# POWER.net
KiCad netlist of a schematic drawn in Altium Designer
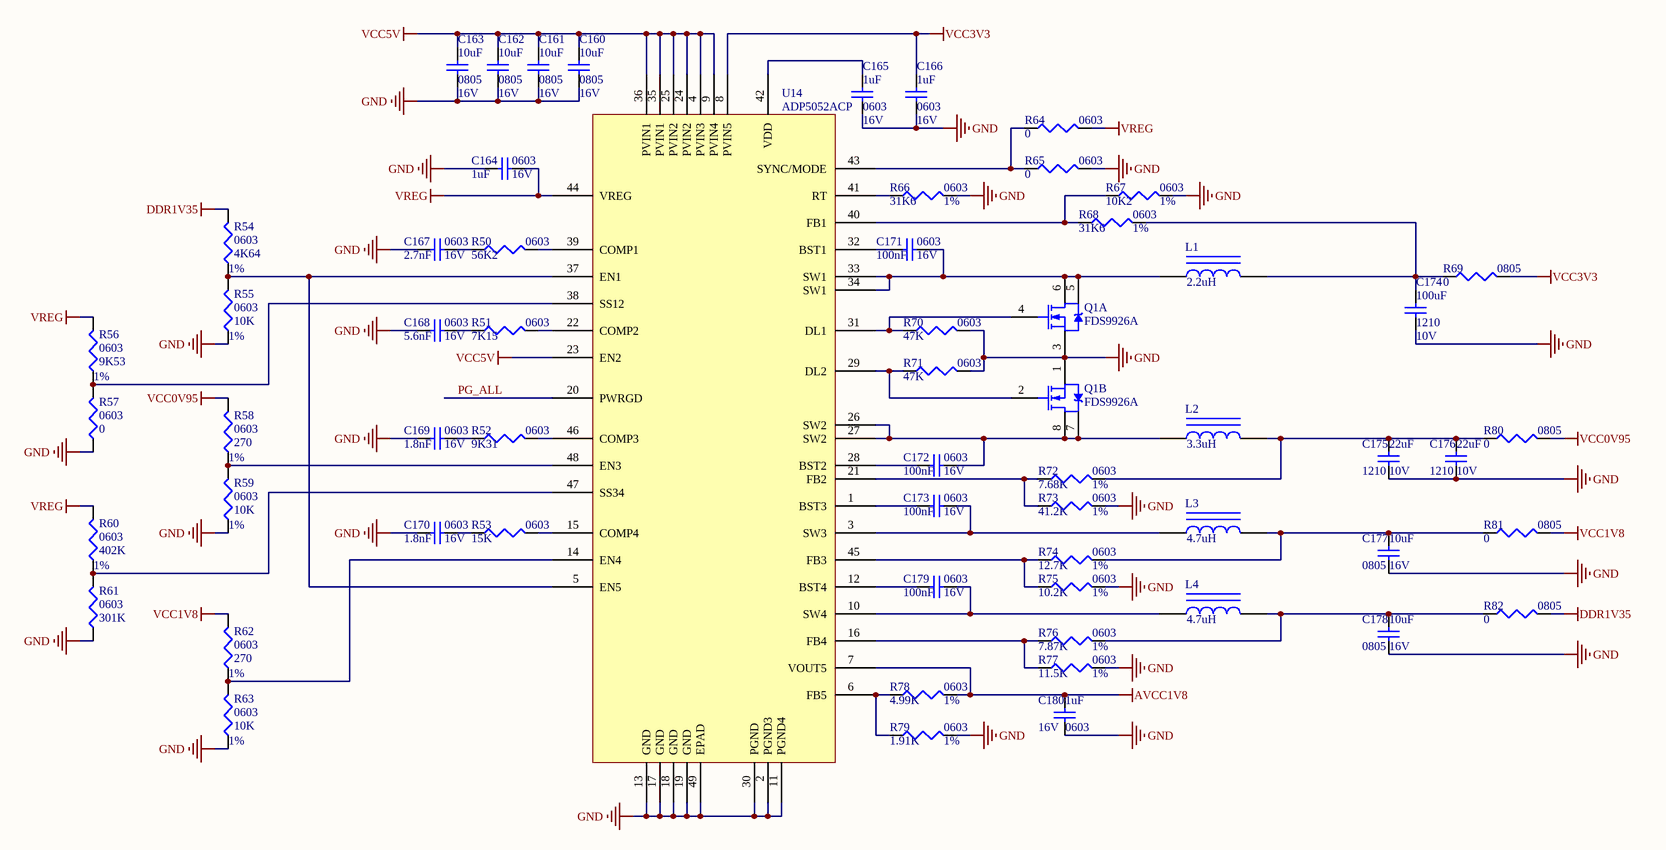
[diagram p0: POWER.SchDoc]

(export (version "E")
  (design (tool "Eeschema 10.0.6"))
  (components
    (comp (ref "C160")
      (value "10uF")
      (footprint "2012[0805]")
      (description "Capacitor (Semiconductor SIM Model)")
      (fields
        (field (name "PACKAGEREFERENCE") "0805")
        (field (name "V") "16V")
        (field (name "PUBLISHER") "Altium Limited")
      )
      (libsource (lib "Devices") (part "Cap Semi"))
    )
    (comp (ref "C161")
      (value "10uF")
      (footprint "2012[0805]")
      (description "Capacitor (Semiconductor SIM Model)")
      (fields
        (field (name "PACKAGEREFERENCE") "0805")
        (field (name "V") "16V")
        (field (name "PUBLISHER") "Altium Limited")
      )
      (libsource (lib "Devices") (part "Cap Semi"))
    )
    (comp (ref "C162")
      (value "10uF")
      (footprint "2012[0805]")
      (description "Capacitor (Semiconductor SIM Model)")
      (fields
        (field (name "PACKAGEREFERENCE") "0805")
        (field (name "V") "16V")
        (field (name "PUBLISHER") "Altium Limited")
      )
      (libsource (lib "Devices") (part "Cap Semi"))
    )
    (comp (ref "C163")
      (value "10uF")
      (footprint "2012[0805]")
      (description "Capacitor (Semiconductor SIM Model)")
      (fields
        (field (name "PACKAGEREFERENCE") "0805")
        (field (name "V") "16V")
        (field (name "PUBLISHER") "Altium Limited")
      )
      (libsource (lib "Devices") (part "Cap Semi"))
    )
    (comp (ref "C164")
      (value "1uF")
      (footprint "1608[0603]")
      (description "Capacitor (Semiconductor SIM Model)")
      (fields
        (field (name "PACKAGEREFERENCE") "0603")
        (field (name "V") "16V")
        (field (name "PUBLISHER") "Altium Limited")
      )
      (libsource (lib "Devices") (part "Cap Semi"))
    )
    (comp (ref "C165")
      (value "1uF")
      (footprint "1608[0603]")
      (description "Capacitor (Semiconductor SIM Model)")
      (fields
        (field (name "PACKAGEREFERENCE") "0603")
        (field (name "V") "16V")
        (field (name "PUBLISHER") "Altium Limited")
      )
      (libsource (lib "Devices") (part "Cap Semi"))
    )
    (comp (ref "C166")
      (value "1uF")
      (footprint "1608[0603]")
      (description "Capacitor (Semiconductor SIM Model)")
      (fields
        (field (name "PACKAGEREFERENCE") "0603")
        (field (name "V") "16V")
        (field (name "PUBLISHER") "Altium Limited")
      )
      (libsource (lib "Devices") (part "Cap Semi"))
    )
    (comp (ref "C167")
      (value "2.7nF")
      (footprint "1608[0603]")
      (description "Capacitor (Semiconductor SIM Model)")
      (fields
        (field (name "PACKAGEREFERENCE") "0603")
        (field (name "V") "16V")
        (field (name "PUBLISHER") "Altium Limited")
      )
      (libsource (lib "Devices") (part "Cap Semi"))
    )
    (comp (ref "C168")
      (value "5.6nF")
      (footprint "1608[0603]")
      (description "Capacitor (Semiconductor SIM Model)")
      (fields
        (field (name "PACKAGEREFERENCE") "0603")
        (field (name "V") "16V")
        (field (name "PUBLISHER") "Altium Limited")
      )
      (libsource (lib "Devices") (part "Cap Semi"))
    )
    (comp (ref "C169")
      (value "1.8nF")
      (footprint "1608[0603]")
      (description "Capacitor (Semiconductor SIM Model)")
      (fields
        (field (name "PACKAGEREFERENCE") "0603")
        (field (name "V") "16V")
        (field (name "PUBLISHER") "Altium Limited")
      )
      (libsource (lib "Devices") (part "Cap Semi"))
    )
    (comp (ref "C170")
      (value "1.8nF")
      (footprint "1608[0603]")
      (description "Capacitor (Semiconductor SIM Model)")
      (fields
        (field (name "PACKAGEREFERENCE") "0603")
        (field (name "V") "16V")
        (field (name "PUBLISHER") "Altium Limited")
      )
      (libsource (lib "Devices") (part "Cap Semi"))
    )
    (comp (ref "C171")
      (value "100nF")
      (footprint "1608[0603]")
      (description "Capacitor (Semiconductor SIM Model)")
      (fields
        (field (name "PACKAGEREFERENCE") "0603")
        (field (name "V") "16V")
        (field (name "PUBLISHER") "Altium Limited")
      )
      (libsource (lib "Devices") (part "Cap Semi"))
    )
    (comp (ref "C172")
      (value "100nF")
      (footprint "1608[0603]")
      (description "Capacitor (Semiconductor SIM Model)")
      (fields
        (field (name "PACKAGEREFERENCE") "0603")
        (field (name "V") "16V")
        (field (name "PUBLISHER") "Altium Limited")
      )
      (libsource (lib "Devices") (part "Cap Semi"))
    )
    (comp (ref "C173")
      (value "100nF")
      (footprint "1608[0603]")
      (description "Capacitor (Semiconductor SIM Model)")
      (fields
        (field (name "PACKAGEREFERENCE") "0603")
        (field (name "V") "16V")
        (field (name "PUBLISHER") "Altium Limited")
      )
      (libsource (lib "Devices") (part "Cap Semi"))
    )
    (comp (ref "C174")
      (value "100uF")
      (footprint "2012[0805]")
      (description "Capacitor (Semiconductor SIM Model)")
      (fields
        (field (name "PACKAGEREFERENCE") "1210")
        (field (name "V") "10V")
        (field (name "PUBLISHER") "Altium Limited")
      )
      (libsource (lib "Devices") (part "Cap Semi"))
    )
    (comp (ref "C175")
      (value "22uF")
      (footprint "2012[0805]")
      (description "Capacitor (Semiconductor SIM Model)")
      (fields
        (field (name "PACKAGEREFERENCE") "1210")
        (field (name "V") "10V")
        (field (name "PUBLISHER") "Altium Limited")
      )
      (libsource (lib "Devices") (part "Cap Semi"))
    )
    (comp (ref "C176")
      (value "22uF")
      (footprint "2012[0805]")
      (description "Capacitor (Semiconductor SIM Model)")
      (fields
        (field (name "PACKAGEREFERENCE") "1210")
        (field (name "V") "10V")
        (field (name "PUBLISHER") "Altium Limited")
      )
      (libsource (lib "Devices") (part "Cap Semi"))
    )
    (comp (ref "C177")
      (value "10uF")
      (footprint "2012[0805]")
      (description "Capacitor (Semiconductor SIM Model)")
      (fields
        (field (name "PACKAGEREFERENCE") "0805")
        (field (name "V") "16V")
        (field (name "PUBLISHER") "Altium Limited")
      )
      (libsource (lib "Devices") (part "Cap Semi"))
    )
    (comp (ref "C178")
      (value "10uF")
      (footprint "2012[0805]")
      (description "Capacitor (Semiconductor SIM Model)")
      (fields
        (field (name "PACKAGEREFERENCE") "0805")
        (field (name "V") "16V")
        (field (name "PUBLISHER") "Altium Limited")
      )
      (libsource (lib "Devices") (part "Cap Semi"))
    )
    (comp (ref "C179")
      (value "100nF")
      (footprint "1608[0603]")
      (description "Capacitor (Semiconductor SIM Model)")
      (fields
        (field (name "PACKAGEREFERENCE") "0603")
        (field (name "V") "16V")
        (field (name "PUBLISHER") "Altium Limited")
      )
      (libsource (lib "Devices") (part "Cap Semi"))
    )
    (comp (ref "C180")
      (value "1uF")
      (footprint "1608[0603]")
      (description "Capacitor (Semiconductor SIM Model)")
      (fields
        (field (name "PACKAGEREFERENCE") "0603")
        (field (name "V") "16V")
        (field (name "PUBLISHER") "Altium Limited")
      )
      (libsource (lib "Devices") (part "Cap Semi"))
    )
    (comp (ref "L1")
      (value "2.2uH")
      (footprint "SRN6045")
      (description "Magnetic-Core Inductor")
      (fields (field (name "Comment") "Inductor Iron") (field (name "PUBLISHER") "Altium Limited"))
      (libsource (lib "Miscellaneous Devices") (part "Inductor Iron"))
    )
    (comp (ref "L2")
      (value "3.3uH")
      (footprint "SRN4018")
      (description "Magnetic-Core Inductor")
      (fields (field (name "Comment") "Inductor Iron") (field (name "PUBLISHER") "Altium Limited"))
      (libsource (lib "Miscellaneous Devices") (part "Inductor Iron"))
    )
    (comp (ref "L3")
      (value "4.7uH")
      (footprint "SRN4018")
      (description "Magnetic-Core Inductor")
      (fields (field (name "Comment") "Inductor Iron") (field (name "PUBLISHER") "Altium Limited"))
      (libsource (lib "Miscellaneous Devices") (part "Inductor Iron"))
    )
    (comp (ref "L4")
      (value "4.7uH")
      (footprint "SRN4018")
      (description "Magnetic-Core Inductor")
      (fields (field (name "Comment") "Inductor Iron") (field (name "PUBLISHER") "Altium Limited"))
      (libsource (lib "Miscellaneous Devices") (part "Inductor Iron"))
    )
    (comp (ref "Q1")
      (value "FDS9926A")
      (footprint "FDS9926A")
      (libsource (lib "Spartan6_LX9_A0") (part "FDS9926A"))
    )
    (comp (ref "R50")
      (value "56K2")
      (footprint "1608[0603]")
      (description "Resistor")
      (fields
        (field (name "PACKAGEREFERENCE") "0603")
        (field (name "Comment") "Res3")
        (field (name "PUBLISHER") "Altium Limited")
      )
      (libsource (lib "Miscellaneous Devices") (part "Res3"))
    )
    (comp (ref "R51")
      (value "7K15")
      (footprint "1608[0603]")
      (description "Resistor")
      (fields
        (field (name "PACKAGEREFERENCE") "0603")
        (field (name "Comment") "Res3")
        (field (name "PUBLISHER") "Altium Limited")
      )
      (libsource (lib "Miscellaneous Devices") (part "Res3"))
    )
    (comp (ref "R52")
      (value "9K31")
      (footprint "1608[0603]")
      (description "Resistor")
      (fields
        (field (name "PACKAGEREFERENCE") "0603")
        (field (name "Comment") "Res3")
        (field (name "PUBLISHER") "Altium Limited")
      )
      (libsource (lib "Miscellaneous Devices") (part "Res3"))
    )
    (comp (ref "R53")
      (value "15K")
      (footprint "1608[0603]")
      (description "Resistor")
      (fields
        (field (name "PACKAGEREFERENCE") "0603")
        (field (name "Comment") "Res3")
        (field (name "PUBLISHER") "Altium Limited")
      )
      (libsource (lib "Miscellaneous Devices") (part "Res3"))
    )
    (comp (ref "R54")
      (value "4K64")
      (footprint "1608[0603]")
      (description "Resistor")
      (fields
        (field (name "PACKAGEREFERENCE") "0603")
        (field (name "AC") "1%")
        (field (name "Comment") "Res3")
        (field (name "PUBLISHER") "Altium Limited")
      )
      (libsource (lib "Miscellaneous Devices") (part "Res3"))
    )
    (comp (ref "R55")
      (value "10K")
      (footprint "1608[0603]")
      (description "Resistor")
      (fields
        (field (name "PACKAGEREFERENCE") "0603")
        (field (name "AC") "1%")
        (field (name "Comment") "Res3")
        (field (name "PUBLISHER") "Altium Limited")
      )
      (libsource (lib "Miscellaneous Devices") (part "Res3"))
    )
    (comp (ref "R56")
      (value "9K53")
      (footprint "1608[0603]")
      (description "Resistor")
      (fields
        (field (name "PACKAGEREFERENCE") "0603")
        (field (name "AC") "1%")
        (field (name "Comment") "Res3")
        (field (name "PUBLISHER") "Altium Limited")
      )
      (libsource (lib "Miscellaneous Devices") (part "Res3"))
    )
    (comp (ref "R57")
      (value "0")
      (footprint "1608[0603]")
      (description "Resistor")
      (fields
        (field (name "PACKAGEREFERENCE") "0603")
        (field (name "Comment") "Res3")
        (field (name "PUBLISHER") "Altium Limited")
      )
      (libsource (lib "Miscellaneous Devices") (part "Res3"))
    )
    (comp (ref "R58")
      (value "270")
      (footprint "1608[0603]")
      (description "Resistor")
      (fields
        (field (name "PACKAGEREFERENCE") "0603")
        (field (name "AC") "1%")
        (field (name "Comment") "Res3")
        (field (name "PUBLISHER") "Altium Limited")
      )
      (libsource (lib "Miscellaneous Devices") (part "Res3"))
    )
    (comp (ref "R59")
      (value "10K")
      (footprint "1608[0603]")
      (description "Resistor")
      (fields
        (field (name "PACKAGEREFERENCE") "0603")
        (field (name "AC") "1%")
        (field (name "Comment") "Res3")
        (field (name "PUBLISHER") "Altium Limited")
      )
      (libsource (lib "Miscellaneous Devices") (part "Res3"))
    )
    (comp (ref "R60")
      (value "402K")
      (footprint "1608[0603]")
      (description "Resistor")
      (fields
        (field (name "PACKAGEREFERENCE") "0603")
        (field (name "AC") "1%")
        (field (name "Comment") "Res3")
        (field (name "PUBLISHER") "Altium Limited")
      )
      (libsource (lib "Miscellaneous Devices") (part "Res3"))
    )
    (comp (ref "R61")
      (value "301K")
      (footprint "1608[0603]")
      (description "Resistor")
      (fields
        (field (name "PACKAGEREFERENCE") "0603")
        (field (name "Comment") "Res3")
        (field (name "PUBLISHER") "Altium Limited")
      )
      (libsource (lib "Miscellaneous Devices") (part "Res3"))
    )
    (comp (ref "R62")
      (value "270")
      (footprint "1608[0603]")
      (description "Resistor")
      (fields
        (field (name "PACKAGEREFERENCE") "0603")
        (field (name "AC") "1%")
        (field (name "Comment") "Res3")
        (field (name "PUBLISHER") "Altium Limited")
      )
      (libsource (lib "Miscellaneous Devices") (part "Res3"))
    )
    (comp (ref "R63")
      (value "10K")
      (footprint "1608[0603]")
      (description "Resistor")
      (fields
        (field (name "PACKAGEREFERENCE") "0603")
        (field (name "AC") "1%")
        (field (name "Comment") "Res3")
        (field (name "PUBLISHER") "Altium Limited")
      )
      (libsource (lib "Miscellaneous Devices") (part "Res3"))
    )
    (comp (ref "R64")
      (value "0")
      (footprint "1608[0603]")
      (description "Resistor")
      (fields
        (field (name "PACKAGEREFERENCE") "0603")
        (field (name "Comment") "Res3")
        (field (name "PUBLISHER") "Altium Limited")
      )
      (libsource (lib "Miscellaneous Devices") (part "Res3"))
    )
    (comp (ref "R65")
      (value "0")
      (footprint "1608[0603]")
      (description "Resistor")
      (fields
        (field (name "PACKAGEREFERENCE") "0603")
        (field (name "Comment") "Res3")
        (field (name "PUBLISHER") "Altium Limited")
      )
      (libsource (lib "Miscellaneous Devices") (part "Res3"))
    )
    (comp (ref "R66")
      (value "31K6")
      (footprint "1608[0603]")
      (description "Resistor")
      (fields
        (field (name "PACKAGEREFERENCE") "0603")
        (field (name "AC") "1%")
        (field (name "Comment") "Res3")
        (field (name "PUBLISHER") "Altium Limited")
      )
      (libsource (lib "Miscellaneous Devices") (part "Res3"))
    )
    (comp (ref "R67")
      (value "10K2")
      (footprint "1608[0603]")
      (description "Resistor")
      (fields
        (field (name "PACKAGEREFERENCE") "0603")
        (field (name "AC") "1%")
        (field (name "Comment") "Res3")
        (field (name "PUBLISHER") "Altium Limited")
      )
      (libsource (lib "Miscellaneous Devices") (part "Res3"))
    )
    (comp (ref "R68")
      (value "31K6")
      (footprint "1608[0603]")
      (description "Resistor")
      (fields
        (field (name "PACKAGEREFERENCE") "0603")
        (field (name "AC") "1%")
        (field (name "Comment") "Res3")
        (field (name "PUBLISHER") "Altium Limited")
      )
      (libsource (lib "Miscellaneous Devices") (part "Res3"))
    )
    (comp (ref "R69")
      (value "0")
      (footprint "2012[0805]")
      (description "Resistor")
      (fields
        (field (name "PACKAGEREFERENCE") "0805")
        (field (name "Comment") "Res3")
        (field (name "PUBLISHER") "Altium Limited")
      )
      (libsource (lib "Miscellaneous Devices") (part "Res3"))
    )
    (comp (ref "R70")
      (value "47K")
      (footprint "1608[0603]")
      (description "Resistor")
      (fields
        (field (name "PACKAGEREFERENCE") "0603")
        (field (name "Comment") "Res3")
        (field (name "PUBLISHER") "Altium Limited")
      )
      (libsource (lib "Miscellaneous Devices") (part "Res3"))
    )
    (comp (ref "R71")
      (value "47K")
      (footprint "1608[0603]")
      (description "Resistor")
      (fields
        (field (name "PACKAGEREFERENCE") "0603")
        (field (name "Comment") "Res3")
        (field (name "PUBLISHER") "Altium Limited")
      )
      (libsource (lib "Miscellaneous Devices") (part "Res3"))
    )
    (comp (ref "R72")
      (value "7.68K")
      (footprint "1608[0603]")
      (description "Resistor")
      (fields
        (field (name "PACKAGEREFERENCE") "0603")
        (field (name "AC") "1%")
        (field (name "Comment") "Res3")
        (field (name "PUBLISHER") "Altium Limited")
      )
      (libsource (lib "Miscellaneous Devices") (part "Res3"))
    )
    (comp (ref "R73")
      (value "41.2K")
      (footprint "1608[0603]")
      (description "Resistor")
      (fields
        (field (name "PACKAGEREFERENCE") "0603")
        (field (name "AC") "1%")
        (field (name "Comment") "Res3")
        (field (name "PUBLISHER") "Altium Limited")
      )
      (libsource (lib "Miscellaneous Devices") (part "Res3"))
    )
    (comp (ref "R74")
      (value "12.7K")
      (footprint "1608[0603]")
      (description "Resistor")
      (fields
        (field (name "PACKAGEREFERENCE") "0603")
        (field (name "AC") "1%")
        (field (name "Comment") "Res3")
        (field (name "PUBLISHER") "Altium Limited")
      )
      (libsource (lib "Miscellaneous Devices") (part "Res3"))
    )
    (comp (ref "R75")
      (value "10.2K")
      (footprint "1608[0603]")
      (description "Resistor")
      (fields
        (field (name "PACKAGEREFERENCE") "0603")
        (field (name "AC") "1%")
        (field (name "Comment") "Res3")
        (field (name "PUBLISHER") "Altium Limited")
      )
      (libsource (lib "Miscellaneous Devices") (part "Res3"))
    )
    (comp (ref "R76")
      (value "7.87K")
      (footprint "1608[0603]")
      (description "Resistor")
      (fields
        (field (name "PACKAGEREFERENCE") "0603")
        (field (name "AC") "1%")
        (field (name "Comment") "Res3")
        (field (name "PUBLISHER") "Altium Limited")
      )
      (libsource (lib "Miscellaneous Devices") (part "Res3"))
    )
    (comp (ref "R77")
      (value "11.5K")
      (footprint "1608[0603]")
      (description "Resistor")
      (fields
        (field (name "PACKAGEREFERENCE") "0603")
        (field (name "AC") "1%")
        (field (name "Comment") "Res3")
        (field (name "PUBLISHER") "Altium Limited")
      )
      (libsource (lib "Miscellaneous Devices") (part "Res3"))
    )
    (comp (ref "R78")
      (value "4.99K")
      (footprint "1608[0603]")
      (description "Resistor")
      (fields
        (field (name "PACKAGEREFERENCE") "0603")
        (field (name "AC") "1%")
        (field (name "Comment") "Res3")
        (field (name "PUBLISHER") "Altium Limited")
      )
      (libsource (lib "Miscellaneous Devices") (part "Res3"))
    )
    (comp (ref "R79")
      (value "1.91K")
      (footprint "1608[0603]")
      (description "Resistor")
      (fields
        (field (name "PACKAGEREFERENCE") "0603")
        (field (name "AC") "1%")
        (field (name "Comment") "Res3")
        (field (name "PUBLISHER") "Altium Limited")
      )
      (libsource (lib "Miscellaneous Devices") (part "Res3"))
    )
    (comp (ref "R80")
      (value "0")
      (footprint "2012[0805]")
      (description "Resistor")
      (fields
        (field (name "PACKAGEREFERENCE") "0805")
        (field (name "Comment") "Res3")
        (field (name "PUBLISHER") "Altium Limited")
      )
      (libsource (lib "Miscellaneous Devices") (part "Res3"))
    )
    (comp (ref "R81")
      (value "0")
      (footprint "2012[0805]")
      (description "Resistor")
      (fields
        (field (name "PACKAGEREFERENCE") "0805")
        (field (name "Comment") "Res3")
        (field (name "PUBLISHER") "Altium Limited")
      )
      (libsource (lib "Miscellaneous Devices") (part "Res3"))
    )
    (comp (ref "R82")
      (value "0")
      (footprint "2012[0805]")
      (description "Resistor")
      (fields
        (field (name "PACKAGEREFERENCE") "0805")
        (field (name "Comment") "Res3")
        (field (name "PUBLISHER") "Altium Limited")
      )
      (libsource (lib "Miscellaneous Devices") (part "Res3"))
    )
    (comp (ref "U14")
      (value "ADP5052ACP")
      (footprint "ADP5052")
      (libsource (lib "Spartan6_LX9_A0") (part "ADP5052ACP{backslash}"))
    )
  )
  (nets
    (net (code "1") (name "/PG_ALL") (class "Default")
      (node (ref "U14") (pin "20") (pinfunction "PWRGD_20") (pintype "passive"))
    )
    (net (code "2") (name "AVCC1V8") (class "Default")
      (node (ref "C180") (pin "1") (pinfunction "1_1") (pintype "passive"))
      (node (ref "R78") (pin "2") (pinfunction "2_2") (pintype "passive"))
      (node (ref "U14") (pin "7") (pinfunction "VOUT5_7") (pintype "passive"))
    )
    (net (code "3") (name "DDR1V35") (class "Default")
      (node (ref "R54") (pin "2") (pinfunction "2_2") (pintype "passive"))
      (node (ref "R82") (pin "2") (pinfunction "2_2") (pintype "passive"))
    )
    (net (code "4") (name "GND") (class "Default")
      (node (ref "C160") (pin "2") (pinfunction "2_2") (pintype "passive"))
      (node (ref "C161") (pin "2") (pinfunction "2_2") (pintype "passive"))
      (node (ref "C162") (pin "2") (pinfunction "2_2") (pintype "passive"))
      (node (ref "C163") (pin "2") (pinfunction "2_2") (pintype "passive"))
      (node (ref "C164") (pin "2") (pinfunction "2_2") (pintype "passive"))
      (node (ref "C165") (pin "2") (pinfunction "2_2") (pintype "passive"))
      (node (ref "C166") (pin "2") (pinfunction "2_2") (pintype "passive"))
      (node (ref "C167") (pin "2") (pinfunction "2_2") (pintype "passive"))
      (node (ref "C168") (pin "2") (pinfunction "2_2") (pintype "passive"))
      (node (ref "C169") (pin "2") (pinfunction "2_2") (pintype "passive"))
      (node (ref "C170") (pin "2") (pinfunction "2_2") (pintype "passive"))
      (node (ref "C174") (pin "1") (pinfunction "1_1") (pintype "passive"))
      (node (ref "C175") (pin "2") (pinfunction "2_2") (pintype "passive"))
      (node (ref "C176") (pin "2") (pinfunction "2_2") (pintype "passive"))
      (node (ref "C177") (pin "2") (pinfunction "2_2") (pintype "passive"))
      (node (ref "C178") (pin "2") (pinfunction "2_2") (pintype "passive"))
      (node (ref "C180") (pin "2") (pinfunction "2_2") (pintype "passive"))
      (node (ref "Q1") (pin "1") (pinfunction "S_1") (pintype "passive"))
      (node (ref "Q1") (pin "3") (pinfunction "S_3") (pintype "passive"))
      (node (ref "R55") (pin "1") (pinfunction "1_1") (pintype "passive"))
      (node (ref "R57") (pin "1") (pinfunction "1_1") (pintype "passive"))
      (node (ref "R59") (pin "1") (pinfunction "1_1") (pintype "passive"))
      (node (ref "R61") (pin "1") (pinfunction "1_1") (pintype "passive"))
      (node (ref "R63") (pin "1") (pinfunction "1_1") (pintype "passive"))
      (node (ref "R65") (pin "2") (pinfunction "2_2") (pintype "passive"))
      (node (ref "R66") (pin "2") (pinfunction "2_2") (pintype "passive"))
      (node (ref "R67") (pin "2") (pinfunction "2_2") (pintype "passive"))
      (node (ref "R70") (pin "2") (pinfunction "2_2") (pintype "passive"))
      (node (ref "R71") (pin "2") (pinfunction "2_2") (pintype "passive"))
      (node (ref "R73") (pin "2") (pinfunction "2_2") (pintype "passive"))
      (node (ref "R75") (pin "2") (pinfunction "2_2") (pintype "passive"))
      (node (ref "R77") (pin "2") (pinfunction "2_2") (pintype "passive"))
      (node (ref "R79") (pin "2") (pinfunction "2_2") (pintype "passive"))
      (node (ref "U14") (pin "11") (pinfunction "PGND4_11") (pintype "passive"))
      (node (ref "U14") (pin "13") (pinfunction "GND_13") (pintype "passive"))
      (node (ref "U14") (pin "17") (pinfunction "GND_17") (pintype "passive"))
      (node (ref "U14") (pin "18") (pinfunction "GND_18") (pintype "passive"))
      (node (ref "U14") (pin "19") (pinfunction "GND_19") (pintype "passive"))
      (node (ref "U14") (pin "2") (pinfunction "PGND3_2") (pintype "passive"))
      (node (ref "U14") (pin "30") (pinfunction "PGND_30") (pintype "passive"))
      (node (ref "U14") (pin "49") (pinfunction "EPAD_49") (pintype "passive"))
    )
    (net (code "5") (name "Net-(C167-Pad1)") (class "Default")
      (node (ref "C167") (pin "1") (pinfunction "1_1") (pintype "passive"))
      (node (ref "R50") (pin "1") (pinfunction "1_1") (pintype "passive"))
    )
    (net (code "6") (name "Net-(C168-Pad1)") (class "Default")
      (node (ref "C168") (pin "1") (pinfunction "1_1") (pintype "passive"))
      (node (ref "R51") (pin "1") (pinfunction "1_1") (pintype "passive"))
    )
    (net (code "7") (name "Net-(C169-Pad1)") (class "Default")
      (node (ref "C169") (pin "1") (pinfunction "1_1") (pintype "passive"))
      (node (ref "R52") (pin "1") (pinfunction "1_1") (pintype "passive"))
    )
    (net (code "8") (name "Net-(C170-Pad1)") (class "Default")
      (node (ref "C170") (pin "1") (pinfunction "1_1") (pintype "passive"))
      (node (ref "R53") (pin "1") (pinfunction "1_1") (pintype "passive"))
    )
    (net (code "9") (name "Net-(C171-Pad2)") (class "Default")
      (node (ref "C171") (pin "2") (pinfunction "2_2") (pintype "passive"))
      (node (ref "L1") (pin "1") (pinfunction "1_1") (pintype "passive"))
      (node (ref "Q1") (pin "5") (pinfunction "D_5") (pintype "passive"))
      (node (ref "Q1") (pin "6") (pinfunction "D_6") (pintype "passive"))
      (node (ref "U14") (pin "33") (pinfunction "SW1_33") (pintype "passive"))
      (node (ref "U14") (pin "34") (pinfunction "SW1_34") (pintype "passive"))
    )
    (net (code "10") (name "Net-(C172-Pad2)") (class "Default")
      (node (ref "C172") (pin "2") (pinfunction "2_2") (pintype "passive"))
      (node (ref "L2") (pin "1") (pinfunction "1_1") (pintype "passive"))
      (node (ref "Q1") (pin "7") (pinfunction "D_7") (pintype "passive"))
      (node (ref "Q1") (pin "8") (pinfunction "D_8") (pintype "passive"))
      (node (ref "U14") (pin "26") (pinfunction "SW2_26") (pintype "passive"))
      (node (ref "U14") (pin "27") (pinfunction "SW2_27") (pintype "passive"))
    )
    (net (code "11") (name "Net-(C174-Pad2)") (class "Default")
      (node (ref "C174") (pin "2") (pinfunction "2_2") (pintype "passive"))
      (node (ref "L1") (pin "2") (pinfunction "2_2") (pintype "passive"))
      (node (ref "R68") (pin "2") (pinfunction "2_2") (pintype "passive"))
      (node (ref "R69") (pin "1") (pinfunction "1_1") (pintype "passive"))
    )
    (net (code "12") (name "Net-(C175-Pad1)") (class "Default")
      (node (ref "C175") (pin "1") (pinfunction "1_1") (pintype "passive"))
      (node (ref "C176") (pin "1") (pinfunction "1_1") (pintype "passive"))
      (node (ref "L2") (pin "2") (pinfunction "2_2") (pintype "passive"))
      (node (ref "R72") (pin "2") (pinfunction "2_2") (pintype "passive"))
      (node (ref "R80") (pin "1") (pinfunction "1_1") (pintype "passive"))
    )
    (net (code "13") (name "Net-(C177-Pad1)") (class "Default")
      (node (ref "C177") (pin "1") (pinfunction "1_1") (pintype "passive"))
      (node (ref "L3") (pin "2") (pinfunction "2_2") (pintype "passive"))
      (node (ref "R74") (pin "2") (pinfunction "2_2") (pintype "passive"))
      (node (ref "R81") (pin "1") (pinfunction "1_1") (pintype "passive"))
    )
    (net (code "14") (name "Net-(C178-Pad1)") (class "Default")
      (node (ref "C178") (pin "1") (pinfunction "1_1") (pintype "passive"))
      (node (ref "L4") (pin "2") (pinfunction "2_2") (pintype "passive"))
      (node (ref "R76") (pin "2") (pinfunction "2_2") (pintype "passive"))
      (node (ref "R82") (pin "1") (pinfunction "1_1") (pintype "passive"))
    )
    (net (code "15") (name "Net-(Q1A-G)") (class "Default")
      (node (ref "Q1") (pin "4") (pinfunction "G_4") (pintype "passive"))
      (node (ref "R70") (pin "1") (pinfunction "1_1") (pintype "passive"))
      (node (ref "U14") (pin "31") (pinfunction "DL1_31") (pintype "passive"))
    )
    (net (code "16") (name "Net-(Q1B-G)") (class "Default")
      (node (ref "Q1") (pin "2") (pinfunction "G_2") (pintype "passive"))
      (node (ref "R71") (pin "1") (pinfunction "1_1") (pintype "passive"))
      (node (ref "U14") (pin "29") (pinfunction "DL2_29") (pintype "passive"))
    )
    (net (code "17") (name "Net-(U14-BST1)") (class "Default")
      (node (ref "C171") (pin "1") (pinfunction "1_1") (pintype "passive"))
      (node (ref "U14") (pin "32") (pinfunction "BST1_32") (pintype "passive"))
    )
    (net (code "18") (name "Net-(U14-BST2)") (class "Default")
      (node (ref "C172") (pin "1") (pinfunction "1_1") (pintype "passive"))
      (node (ref "U14") (pin "28") (pinfunction "BST2_28") (pintype "passive"))
    )
    (net (code "19") (name "Net-(U14-BST3)") (class "Default")
      (node (ref "C173") (pin "1") (pinfunction "1_1") (pintype "passive"))
      (node (ref "U14") (pin "1") (pinfunction "BST3_1") (pintype "passive"))
    )
    (net (code "20") (name "Net-(U14-BST4)") (class "Default")
      (node (ref "C179") (pin "1") (pinfunction "1_1") (pintype "passive"))
      (node (ref "U14") (pin "12") (pinfunction "BST4_12") (pintype "passive"))
    )
    (net (code "21") (name "Net-(U14-COMP1)") (class "Default")
      (node (ref "R50") (pin "2") (pinfunction "2_2") (pintype "passive"))
      (node (ref "U14") (pin "39") (pinfunction "COMP1_39") (pintype "passive"))
    )
    (net (code "22") (name "Net-(U14-COMP2)") (class "Default")
      (node (ref "R51") (pin "2") (pinfunction "2_2") (pintype "passive"))
      (node (ref "U14") (pin "22") (pinfunction "COMP2_22") (pintype "passive"))
    )
    (net (code "23") (name "Net-(U14-COMP3)") (class "Default")
      (node (ref "R52") (pin "2") (pinfunction "2_2") (pintype "passive"))
      (node (ref "U14") (pin "46") (pinfunction "COMP3_46") (pintype "passive"))
    )
    (net (code "24") (name "Net-(U14-COMP4)") (class "Default")
      (node (ref "R53") (pin "2") (pinfunction "2_2") (pintype "passive"))
      (node (ref "U14") (pin "15") (pinfunction "COMP4_15") (pintype "passive"))
    )
    (net (code "25") (name "Net-(U14-EN1)") (class "Default")
      (node (ref "R54") (pin "1") (pinfunction "1_1") (pintype "passive"))
      (node (ref "R55") (pin "2") (pinfunction "2_2") (pintype "passive"))
      (node (ref "U14") (pin "37") (pinfunction "EN1_37") (pintype "passive"))
      (node (ref "U14") (pin "5") (pinfunction "EN5_5") (pintype "passive"))
    )
    (net (code "26") (name "Net-(U14-EN3)") (class "Default")
      (node (ref "R58") (pin "1") (pinfunction "1_1") (pintype "passive"))
      (node (ref "R59") (pin "2") (pinfunction "2_2") (pintype "passive"))
      (node (ref "U14") (pin "48") (pinfunction "EN3_48") (pintype "passive"))
    )
    (net (code "27") (name "Net-(U14-EN4)") (class "Default")
      (node (ref "R62") (pin "1") (pinfunction "1_1") (pintype "passive"))
      (node (ref "R63") (pin "2") (pinfunction "2_2") (pintype "passive"))
      (node (ref "U14") (pin "14") (pinfunction "EN4_14") (pintype "passive"))
    )
    (net (code "28") (name "Net-(U14-FB1)") (class "Default")
      (node (ref "R67") (pin "1") (pinfunction "1_1") (pintype "passive"))
      (node (ref "R68") (pin "1") (pinfunction "1_1") (pintype "passive"))
      (node (ref "U14") (pin "40") (pinfunction "FB1_40") (pintype "passive"))
    )
    (net (code "29") (name "Net-(U14-FB2)") (class "Default")
      (node (ref "R72") (pin "1") (pinfunction "1_1") (pintype "passive"))
      (node (ref "R73") (pin "1") (pinfunction "1_1") (pintype "passive"))
      (node (ref "U14") (pin "21") (pinfunction "FB2_21") (pintype "passive"))
    )
    (net (code "30") (name "Net-(U14-FB3)") (class "Default")
      (node (ref "R74") (pin "1") (pinfunction "1_1") (pintype "passive"))
      (node (ref "R75") (pin "1") (pinfunction "1_1") (pintype "passive"))
      (node (ref "U14") (pin "45") (pinfunction "FB3_45") (pintype "passive"))
    )
    (net (code "31") (name "Net-(U14-FB4)") (class "Default")
      (node (ref "R76") (pin "1") (pinfunction "1_1") (pintype "passive"))
      (node (ref "R77") (pin "1") (pinfunction "1_1") (pintype "passive"))
      (node (ref "U14") (pin "16") (pinfunction "FB4_16") (pintype "passive"))
    )
    (net (code "32") (name "Net-(U14-FB5)") (class "Default")
      (node (ref "R78") (pin "1") (pinfunction "1_1") (pintype "passive"))
      (node (ref "R79") (pin "1") (pinfunction "1_1") (pintype "passive"))
      (node (ref "U14") (pin "6") (pinfunction "FB5_6") (pintype "passive"))
    )
    (net (code "33") (name "Net-(U14-RT)") (class "Default")
      (node (ref "R66") (pin "1") (pinfunction "1_1") (pintype "passive"))
      (node (ref "U14") (pin "41") (pinfunction "RT_41") (pintype "passive"))
    )
    (net (code "34") (name "Net-(U14-SS12)") (class "Default")
      (node (ref "R56") (pin "1") (pinfunction "1_1") (pintype "passive"))
      (node (ref "R57") (pin "2") (pinfunction "2_2") (pintype "passive"))
      (node (ref "U14") (pin "38") (pinfunction "SS12_38") (pintype "passive"))
    )
    (net (code "35") (name "Net-(U14-SS34)") (class "Default")
      (node (ref "R60") (pin "1") (pinfunction "1_1") (pintype "passive"))
      (node (ref "R61") (pin "2") (pinfunction "2_2") (pintype "passive"))
      (node (ref "U14") (pin "47") (pinfunction "SS34_47") (pintype "passive"))
    )
    (net (code "36") (name "Net-(U14-SW3)") (class "Default")
      (node (ref "C173") (pin "2") (pinfunction "2_2") (pintype "passive"))
      (node (ref "L3") (pin "1") (pinfunction "1_1") (pintype "passive"))
      (node (ref "U14") (pin "3") (pinfunction "SW3_3") (pintype "passive"))
    )
    (net (code "37") (name "Net-(U14-SW4)") (class "Default")
      (node (ref "C179") (pin "2") (pinfunction "2_2") (pintype "passive"))
      (node (ref "L4") (pin "1") (pinfunction "1_1") (pintype "passive"))
      (node (ref "U14") (pin "10") (pinfunction "SW4_10") (pintype "passive"))
    )
    (net (code "38") (name "Net-(U14-SYNC{slash}MODE)") (class "Default")
      (node (ref "R64") (pin "1") (pinfunction "1_1") (pintype "passive"))
      (node (ref "R65") (pin "1") (pinfunction "1_1") (pintype "passive"))
      (node (ref "U14") (pin "43") (pinfunction "SYNC/MODE_43") (pintype "passive"))
    )
    (net (code "39") (name "Net-(U14-VDD)") (class "Default")
      (node (ref "C165") (pin "1") (pinfunction "1_1") (pintype "passive"))
      (node (ref "U14") (pin "42") (pinfunction "VDD_42") (pintype "passive"))
    )
    (net (code "40") (name "VCC0V95") (class "Default")
      (node (ref "R58") (pin "2") (pinfunction "2_2") (pintype "passive"))
      (node (ref "R80") (pin "2") (pinfunction "2_2") (pintype "passive"))
    )
    (net (code "41") (name "VCC1V8") (class "Default")
      (node (ref "R62") (pin "2") (pinfunction "2_2") (pintype "passive"))
      (node (ref "R81") (pin "2") (pinfunction "2_2") (pintype "passive"))
    )
    (net (code "42") (name "VCC3V3") (class "Default")
      (node (ref "C166") (pin "1") (pinfunction "1_1") (pintype "passive"))
      (node (ref "R69") (pin "2") (pinfunction "2_2") (pintype "passive"))
      (node (ref "U14") (pin "8") (pinfunction "PVIN5_8") (pintype "passive"))
    )
    (net (code "43") (name "VCC5V") (class "Default")
      (node (ref "C160") (pin "1") (pinfunction "1_1") (pintype "passive"))
      (node (ref "C161") (pin "1") (pinfunction "1_1") (pintype "passive"))
      (node (ref "C162") (pin "1") (pinfunction "1_1") (pintype "passive"))
      (node (ref "C163") (pin "1") (pinfunction "1_1") (pintype "passive"))
      (node (ref "U14") (pin "23") (pinfunction "EN2_23") (pintype "passive"))
      (node (ref "U14") (pin "24") (pinfunction "PVIN2_24") (pintype "passive"))
      (node (ref "U14") (pin "25") (pinfunction "PVIN2_25") (pintype "passive"))
      (node (ref "U14") (pin "35") (pinfunction "PVIN1_35") (pintype "passive"))
      (node (ref "U14") (pin "36") (pinfunction "PVIN1_36") (pintype "passive"))
      (node (ref "U14") (pin "4") (pinfunction "PVIN3_4") (pintype "passive"))
      (node (ref "U14") (pin "9") (pinfunction "PVIN4_9") (pintype "passive"))
    )
    (net (code "44") (name "VREG") (class "Default")
      (node (ref "C164") (pin "1") (pinfunction "1_1") (pintype "passive"))
      (node (ref "R56") (pin "2") (pinfunction "2_2") (pintype "passive"))
      (node (ref "R60") (pin "2") (pinfunction "2_2") (pintype "passive"))
      (node (ref "R64") (pin "2") (pinfunction "2_2") (pintype "passive"))
      (node (ref "U14") (pin "44") (pinfunction "VREG_44") (pintype "passive"))
    )
  )
)
